# DD2090_4CAM_FFC_USB.net
KiCad netlist of a schematic drawn in Altium Designer
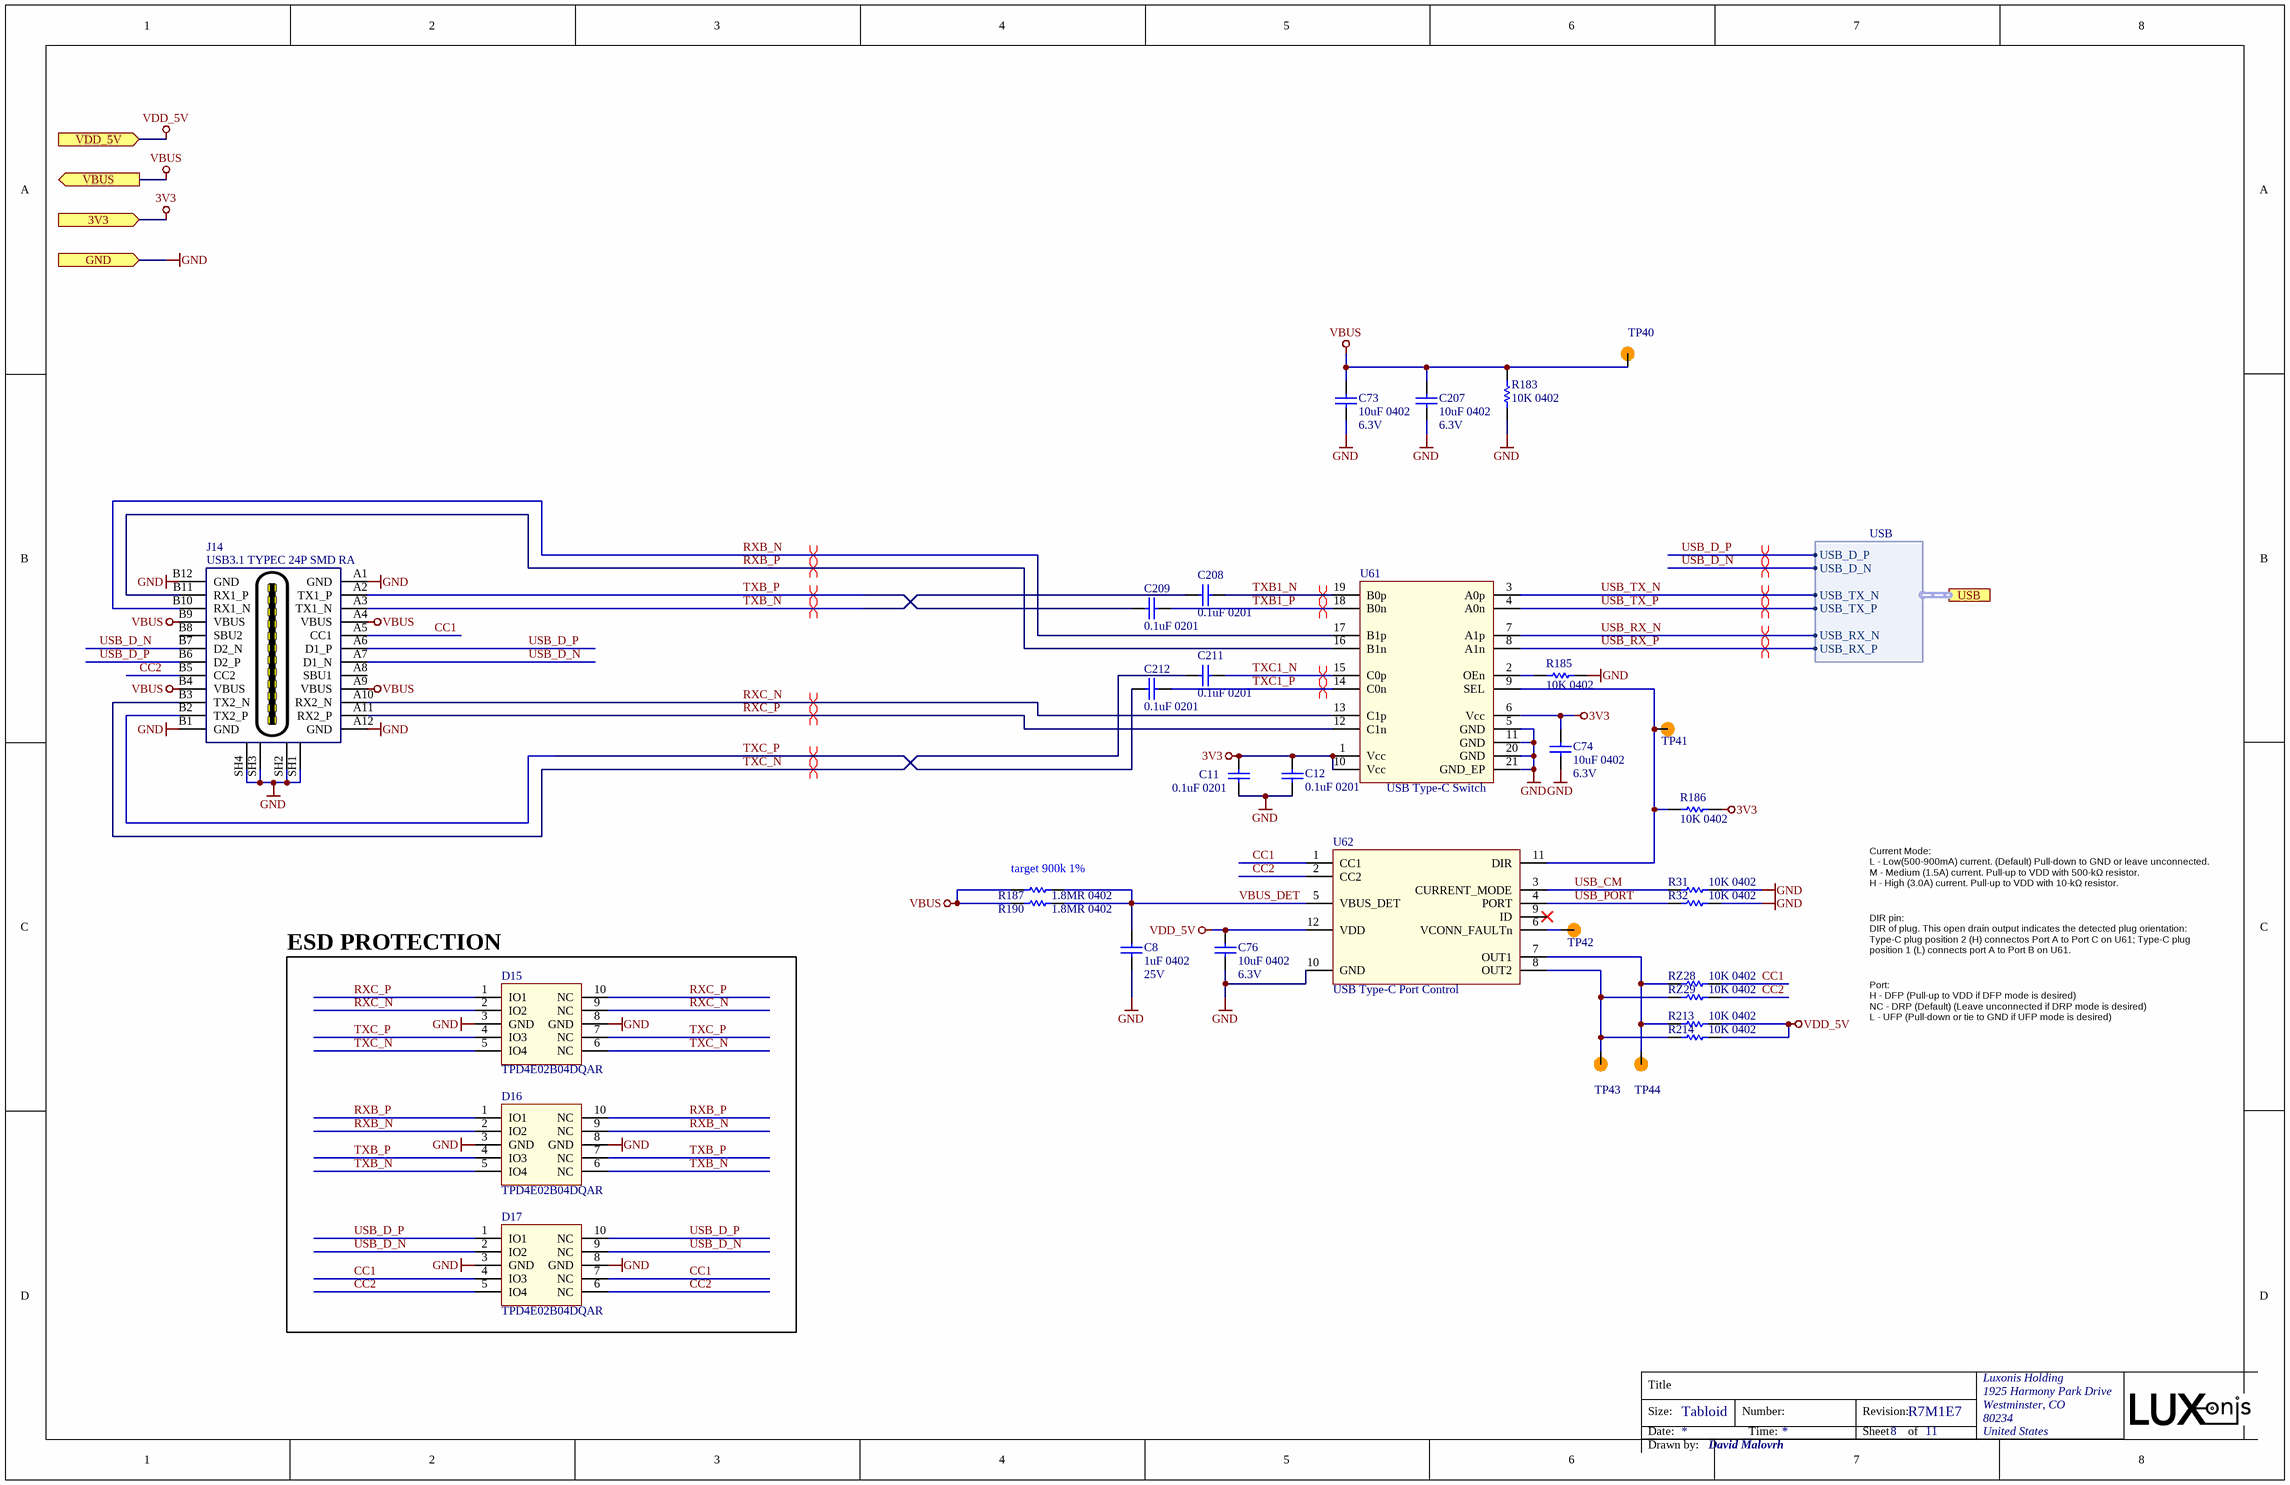
[diagram p0: DD2090_4CAM_FFC_USB.SchDoc]

(export (version "E")
  (design (tool "Eeschema 10.0.6"))
  (components
    (comp (ref "C8")
      (value "1uF 0402")
      (footprint "CAP_Altium_Vault_Generic:CAPC0402(1005)70_N")
      (description "CAP CER 1UF 25V X5R 0402 10%")
      (fields
        (field (name "TOLERANCE") "10%")
        (field (name "VOLTAGE") "25V")
        (field (name "VOLTAGE RATING") "25V")
      )
      (libsource (lib "LuxonisMaster") (part "GRM155R61E105KA12D"))
    )
    (comp (ref "C11")
      (value "0.1uF 0201")
      (footprint "CAP_Altium_Vault_Generic:CAPC0201(0603)33_L")
      (description "CAP CER 0.1UF 10V X5R 0201")
      (fields (field (name "TOLERANCE") "10%") (field (name "VOLTAGE") "10V"))
      (libsource (lib "LuxonisMaster") (part "GRM033R61A104KE15D"))
    )
    (comp (ref "C12")
      (value "0.1uF 0201")
      (footprint "CAP_Altium_Vault_Generic:CAPC0201(0603)33_L")
      (description "CAP CER 0.1UF 10V X5R 0201")
      (fields (field (name "TOLERANCE") "10%") (field (name "VOLTAGE") "10V"))
      (libsource (lib "LuxonisMaster") (part "GRM033R61A104KE15D"))
    )
    (comp (ref "C73")
      (value "10uF 0402")
      (footprint "CAP_Altium_Vault_Generic:CAPC0402(1005)70_N")
      (description "CAP CER 10UF 6.3V X5R 0402 20%")
      (fields (field (name "TOLERANCE") "20%") (field (name "VOLTAGE RATING") "6.3V"))
      (libsource (lib "LuxonisMaster") (part "GRM155R60J106ME15D"))
    )
    (comp (ref "C74")
      (value "10uF 0402")
      (footprint "CAP_Altium_Vault_Generic:CAPC0402(1005)70_N")
      (description "CAP CER 10UF 6.3V X5R 0402 20%")
      (fields (field (name "TOLERANCE") "20%") (field (name "VOLTAGE RATING") "6.3V"))
      (libsource (lib "LuxonisMaster") (part "GRM155R60J106ME15D"))
    )
    (comp (ref "C76")
      (value "10uF 0402")
      (footprint "CAP_Altium_Vault_Generic:CAPC0402(1005)70_N")
      (description "CAP CER 10UF 6.3V X5R 0402 20%")
      (fields (field (name "TOLERANCE") "20%") (field (name "VOLTAGE RATING") "6.3V"))
      (libsource (lib "LuxonisMaster") (part "GRM155R60J106ME15D"))
    )
    (comp (ref "C207")
      (value "10uF 0402")
      (footprint "CAP_Altium_Vault_Generic:CAPC0402(1005)70_N")
      (description "CAP CER 10UF 6.3V X5R 0402 20%")
      (fields (field (name "TOLERANCE") "20%") (field (name "VOLTAGE RATING") "6.3V"))
      (libsource (lib "LuxonisMaster") (part "GRM155R60J106ME15D"))
    )
    (comp (ref "C208")
      (value "0.1uF 0201")
      (footprint "CAP_Altium_Vault_Generic:CAPC0201(0603)33_L")
      (description "CAP CER 0.1UF 10V X5R 0201")
      (fields (field (name "TOLERANCE") "10%") (field (name "VOLTAGE") "10V"))
      (libsource (lib "LuxonisMaster") (part "GRM033R61A104KE15D"))
    )
    (comp (ref "C209")
      (value "0.1uF 0201")
      (footprint "CAP_Altium_Vault_Generic:CAPC0201(0603)33_L")
      (description "CAP CER 0.1UF 10V X5R 0201")
      (fields (field (name "TOLERANCE") "10%") (field (name "VOLTAGE") "10V"))
      (libsource (lib "LuxonisMaster") (part "GRM033R61A104KE15D"))
    )
    (comp (ref "C211")
      (value "0.1uF 0201")
      (footprint "CAP_Altium_Vault_Generic:CAPC0201(0603)33_L")
      (description "CAP CER 0.1UF 10V X5R 0201")
      (fields (field (name "TOLERANCE") "10%") (field (name "VOLTAGE") "10V"))
      (libsource (lib "LuxonisMaster") (part "GRM033R61A104KE15D"))
    )
    (comp (ref "C212")
      (value "0.1uF 0201")
      (footprint "CAP_Altium_Vault_Generic:CAPC0201(0603)33_L")
      (description "CAP CER 0.1UF 10V X5R 0201")
      (fields (field (name "TOLERANCE") "10%") (field (name "VOLTAGE") "10V"))
      (libsource (lib "LuxonisMaster") (part "GRM033R61A104KE15D"))
    )
    (comp (ref "D15")
      (value "TPD4E02B04DQAR")
      (footprint "TPD4E02B04DQAR")
      (libsource (lib "LuxonisMaster") (part "TPD4E02B04DQAR"))
    )
    (comp (ref "D16")
      (value "TPD4E02B04DQAR")
      (footprint "TPD4E02B04DQAR")
      (libsource (lib "LuxonisMaster") (part "TPD4E02B04DQAR"))
    )
    (comp (ref "D17")
      (value "TPD4E02B04DQAR")
      (footprint "TPD4E02B04DQAR")
      (libsource (lib "LuxonisMaster") (part "TPD4E02B04DQAR"))
    )
    (comp (ref "J14")
      (value "USB3.1 TYPEC 24P SMD RA")
      (footprint "LuxonisMaster:105450-0101")
      (description "CONN RCP USB3.1 TYPEC 24P SMD RA")
      (libsource (lib "LuxonisMaster") (part "105450-0101"))
    )
    (comp (ref "R31")
      (value "10K 0402")
      (footprint "RES_Altium_Vault_Generic:RESC0402(1005)_N")
      (fields (field (name "TOLERANCE") "1%"))
      (libsource (lib "LuxonisMaster") (part "RC0402FR-1310KL"))
    )
    (comp (ref "R32")
      (value "10K 0402")
      (footprint "RES_Altium_Vault_Generic:RESC0402(1005)_N")
      (fields (field (name "TOLERANCE") "1%"))
      (libsource (lib "LuxonisMaster") (part "RC0402FR-1310KL"))
    )
    (comp (ref "R183")
      (value "10K 0402")
      (footprint "RES_Altium_Vault_Generic:RESC0402(1005)_N")
      (fields (field (name "TOLERANCE") "1%"))
      (libsource (lib "LuxonisMaster") (part "RC0402FR-1310KL"))
    )
    (comp (ref "R185")
      (value "10K 0402")
      (footprint "RES_Altium_Vault_Generic:RESC0402(1005)_N")
      (fields (field (name "TOLERANCE") "1%"))
      (libsource (lib "LuxonisMaster") (part "RC0402FR-1310KL"))
    )
    (comp (ref "R186")
      (value "10K 0402")
      (footprint "RES_Altium_Vault_Generic:RESC0402(1005)_N")
      (fields (field (name "TOLERANCE") "1%"))
      (libsource (lib "LuxonisMaster") (part "RC0402FR-1310KL"))
    )
    (comp (ref "R187")
      (value "1.8MR 0402")
      (footprint "RES_Altium_Vault_Generic:RESC0402(1005)_N")
      (description "RES SMD 1.8M OHM 1% 1/16W 0402")
      (fields (field (name "TOLERANCE") "1%"))
      (libsource (lib "LuxonisMaster") (part "CRCW04021M80FKED"))
    )
    (comp (ref "R190")
      (value "1.8MR 0402")
      (footprint "RES_Altium_Vault_Generic:RESC0402(1005)_N")
      (description "RES SMD 1.8M OHM 1% 1/16W 0402")
      (fields (field (name "TOLERANCE") "1%"))
      (libsource (lib "LuxonisMaster") (part "CRCW04021M80FKED"))
    )
    (comp (ref "R213")
      (value "10K 0402")
      (footprint "RES_Altium_Vault_Generic:RESC0402(1005)_N")
      (fields (field (name "TOLERANCE") "1%"))
      (libsource (lib "LuxonisMaster") (part "RC0402FR-1310KL"))
    )
    (comp (ref "R214")
      (value "10K 0402")
      (footprint "RES_Altium_Vault_Generic:RESC0402(1005)_N")
      (fields (field (name "TOLERANCE") "1%"))
      (libsource (lib "LuxonisMaster") (part "RC0402FR-1310KL"))
    )
    (comp (ref "RZ28")
      (value "10K 0402")
      (footprint "RES_Altium_Vault_Generic:RESC0402(1005)_N")
      (fields (field (name "TOLERANCE") "1%"))
      (libsource (lib "LuxonisMaster") (part "RC0402FR-1310KL"))
    )
    (comp (ref "RZ29")
      (value "10K 0402")
      (footprint "RES_Altium_Vault_Generic:RESC0402(1005)_N")
      (fields (field (name "TOLERANCE") "1%"))
      (libsource (lib "LuxonisMaster") (part "RC0402FR-1310KL"))
    )
    (comp (ref "TP40")
      (value "TP100_200_NS")
      (footprint "LuxonisMaster:TP100_200_NS")
      (libsource (lib "LuxonisMaster") (part "TEST_POINT"))
    )
    (comp (ref "TP41")
      (value "TP100_200_NS")
      (footprint "LuxonisMaster:TP100_200_NS")
      (libsource (lib "LuxonisMaster") (part "TEST_POINT"))
    )
    (comp (ref "TP42")
      (value "TP100_200_NS")
      (footprint "LuxonisMaster:TP100_200_NS")
      (libsource (lib "LuxonisMaster") (part "TEST_POINT"))
    )
    (comp (ref "TP43")
      (value "TP100_200_NS")
      (footprint "LuxonisMaster:TP100_200_NS")
      (libsource (lib "LuxonisMaster") (part "TEST_POINT"))
    )
    (comp (ref "TP44")
      (value "TP100_200_NS")
      (footprint "LuxonisMaster:TP100_200_NS")
      (libsource (lib "LuxonisMaster") (part "TEST_POINT"))
    )
    (comp (ref "U61")
      (value "USB Type-C Switch")
      (footprint "CBTL02043A")
      (libsource (lib "LuxonisMaster") (part "CBTL02043A"))
    )
    (comp (ref "U62")
      (value "USB Type-C Port Control")
      (footprint "LuxonisMaster:TUSB321RWBR")
      (description "IC USB PORT CONTROL TYPE-C 12X2Q")
      (libsource (lib "LuxonisMaster") (part "TUSB321RWBR"))
    )
  )
  (nets
    (net (code "2") (name "/CC1") (class "Default")
      (node (ref "D17") (pin "4") (pinfunction "IO3_4") (pintype "passive"))
      (node (ref "D17") (pin "7") (pinfunction "NC_7") (pintype "passive"))
      (node (ref "J14") (pin "A5") (pinfunction "CC1_A5") (pintype "passive"))
      (node (ref "RZ28") (pin "2") (pinfunction "2_2") (pintype "passive"))
      (node (ref "U62") (pin "1") (pinfunction "CC1_1") (pintype "passive"))
    )
    (net (code "3") (name "/CC2") (class "Default")
      (node (ref "D17") (pin "5") (pinfunction "IO4_5") (pintype "passive"))
      (node (ref "D17") (pin "6") (pinfunction "NC_6") (pintype "passive"))
      (node (ref "J14") (pin "B5") (pinfunction "CC2_B5") (pintype "passive"))
      (node (ref "RZ29") (pin "2") (pinfunction "2_2") (pintype "passive"))
      (node (ref "U62") (pin "2") (pinfunction "CC2_2") (pintype "passive"))
    )
    (net (code "4") (name "/RXB_N") (class "Default")
      (node (ref "D16") (pin "2") (pinfunction "IO2_2") (pintype "passive"))
      (node (ref "D16") (pin "9") (pinfunction "NC_9") (pintype "passive"))
      (node (ref "J14") (pin "B10") (pinfunction "RX1_N_B10") (pintype "passive"))
      (node (ref "U61") (pin "17") (pinfunction "B1p_17") (pintype "passive"))
    )
    (net (code "5") (name "/RXB_P") (class "Default")
      (node (ref "D16") (pin "1") (pinfunction "IO1_1") (pintype "passive"))
      (node (ref "D16") (pin "10") (pinfunction "NC_10") (pintype "passive"))
      (node (ref "J14") (pin "B11") (pinfunction "RX1_P_B11") (pintype "passive"))
      (node (ref "U61") (pin "16") (pinfunction "B1n_16") (pintype "passive"))
    )
    (net (code "6") (name "/RXC_N") (class "Default")
      (node (ref "D15") (pin "2") (pinfunction "IO2_2") (pintype "passive"))
      (node (ref "D15") (pin "9") (pinfunction "NC_9") (pintype "passive"))
      (node (ref "J14") (pin "A10") (pinfunction "RX2_N_A10") (pintype "passive"))
      (node (ref "U61") (pin "13") (pinfunction "C1p_13") (pintype "passive"))
    )
    (net (code "7") (name "/RXC_P") (class "Default")
      (node (ref "D15") (pin "1") (pinfunction "IO1_1") (pintype "passive"))
      (node (ref "D15") (pin "10") (pinfunction "NC_10") (pintype "passive"))
      (node (ref "J14") (pin "A11") (pinfunction "RX2_P_A11") (pintype "passive"))
      (node (ref "U61") (pin "12") (pinfunction "C1n_12") (pintype "passive"))
    )
    (net (code "8") (name "/TXB1_N") (class "Default")
      (node (ref "C208") (pin "2") (pinfunction "2_2") (pintype "passive"))
      (node (ref "U61") (pin "19") (pinfunction "B0p_19") (pintype "passive"))
    )
    (net (code "9") (name "/TXB1_P") (class "Default")
      (node (ref "C209") (pin "2") (pinfunction "2_2") (pintype "passive"))
      (node (ref "U61") (pin "18") (pinfunction "B0n_18") (pintype "passive"))
    )
    (net (code "10") (name "/TXB_N") (class "Default")
      (node (ref "C208") (pin "1") (pinfunction "1_1") (pintype "passive"))
      (node (ref "D16") (pin "5") (pinfunction "IO4_5") (pintype "passive"))
      (node (ref "D16") (pin "6") (pinfunction "NC_6") (pintype "passive"))
      (node (ref "J14") (pin "A3") (pinfunction "TX1_N_A3") (pintype "passive"))
    )
    (net (code "11") (name "/TXB_P") (class "Default")
      (node (ref "C209") (pin "1") (pinfunction "1_1") (pintype "passive"))
      (node (ref "D16") (pin "4") (pinfunction "IO3_4") (pintype "passive"))
      (node (ref "D16") (pin "7") (pinfunction "NC_7") (pintype "passive"))
      (node (ref "J14") (pin "A2") (pinfunction "TX1_P_A2") (pintype "passive"))
    )
    (net (code "12") (name "/TXC1_N") (class "Default")
      (node (ref "C211") (pin "2") (pinfunction "2_2") (pintype "passive"))
      (node (ref "U61") (pin "15") (pinfunction "C0p_15") (pintype "passive"))
    )
    (net (code "13") (name "/TXC1_P") (class "Default")
      (node (ref "C212") (pin "2") (pinfunction "2_2") (pintype "passive"))
      (node (ref "U61") (pin "14") (pinfunction "C0n_14") (pintype "passive"))
    )
    (net (code "14") (name "/TXC_N") (class "Default")
      (node (ref "C211") (pin "1") (pinfunction "1_1") (pintype "passive"))
      (node (ref "D15") (pin "5") (pinfunction "IO4_5") (pintype "passive"))
      (node (ref "D15") (pin "6") (pinfunction "NC_6") (pintype "passive"))
      (node (ref "J14") (pin "B3") (pinfunction "TX2_N_B3") (pintype "passive"))
    )
    (net (code "15") (name "/TXC_P") (class "Default")
      (node (ref "C212") (pin "1") (pinfunction "1_1") (pintype "passive"))
      (node (ref "D15") (pin "4") (pinfunction "IO3_4") (pintype "passive"))
      (node (ref "D15") (pin "7") (pinfunction "NC_7") (pintype "passive"))
      (node (ref "J14") (pin "B2") (pinfunction "TX2_P_B2") (pintype "passive"))
    )
    (net (code "16") (name "/USB_CM") (class "Default")
      (node (ref "R31") (pin "1") (pinfunction "1_1") (pintype "passive"))
      (node (ref "U62") (pin "3") (pinfunction "CURRENT_MODE_3") (pintype "passive"))
    )
    (net (code "17") (name "/USB_D_N") (class "Default")
      (node (ref "D17") (pin "2") (pinfunction "IO2_2") (pintype "passive"))
      (node (ref "D17") (pin "9") (pinfunction "NC_9") (pintype "passive"))
      (node (ref "J14") (pin "A7") (pinfunction "D1_N_A7") (pintype "passive"))
      (node (ref "J14") (pin "B7") (pinfunction "D2_N_B7") (pintype "passive"))
    )
    (net (code "18") (name "/USB_D_P") (class "Default")
      (node (ref "D17") (pin "1") (pinfunction "IO1_1") (pintype "passive"))
      (node (ref "D17") (pin "10") (pinfunction "NC_10") (pintype "passive"))
      (node (ref "J14") (pin "A6") (pinfunction "D1_P_A6") (pintype "passive"))
      (node (ref "J14") (pin "B6") (pinfunction "D2_P_B6") (pintype "passive"))
    )
    (net (code "19") (name "/USB_PORT") (class "Default")
      (node (ref "R32") (pin "1") (pinfunction "1_1") (pintype "passive"))
      (node (ref "U62") (pin "4") (pinfunction "PORT_4") (pintype "passive"))
    )
    (net (code "20") (name "/USB_RX_N") (class "Default")
      (node (ref "U61") (pin "7") (pinfunction "A1p_7") (pintype "passive"))
    )
    (net (code "21") (name "/USB_RX_P") (class "Default")
      (node (ref "U61") (pin "8") (pinfunction "A1n_8") (pintype "passive"))
    )
    (net (code "22") (name "/USB_TX_N") (class "Default")
      (node (ref "U61") (pin "3") (pinfunction "A0p_3") (pintype "passive"))
    )
    (net (code "23") (name "/USB_TX_P") (class "Default")
      (node (ref "U61") (pin "4") (pinfunction "A0n_4") (pintype "passive"))
    )
    (net (code "24") (name "/VBUS_DET") (class "Default")
      (node (ref "C8") (pin "2") (pinfunction "2_2") (pintype "passive"))
      (node (ref "R187") (pin "2") (pinfunction "2_2") (pintype "passive"))
      (node (ref "R190") (pin "2") (pinfunction "2_2") (pintype "passive"))
      (node (ref "U62") (pin "5") (pinfunction "VBUS_DET_5") (pintype "passive"))
    )
    (net (code "26") (name "3V3") (class "Default")
      (node (ref "C11") (pin "2") (pinfunction "2_2") (pintype "passive"))
      (node (ref "C12") (pin "2") (pinfunction "2_2") (pintype "passive"))
      (node (ref "C74") (pin "2") (pinfunction "2_2") (pintype "passive"))
      (node (ref "R186") (pin "2") (pinfunction "2_2") (pintype "passive"))
      (node (ref "U61") (pin "1") (pinfunction "Vcc_1") (pintype "passive"))
      (node (ref "U61") (pin "10") (pinfunction "Vcc_10") (pintype "passive"))
      (node (ref "U61") (pin "6") (pinfunction "Vcc_6") (pintype "passive"))
    )
    (net (code "27") (name "GND") (class "Default")
      (node (ref "C11") (pin "1") (pinfunction "1_1") (pintype "passive"))
      (node (ref "C12") (pin "1") (pinfunction "1_1") (pintype "passive"))
      (node (ref "C207") (pin "1") (pinfunction "1_1") (pintype "passive"))
      (node (ref "C73") (pin "1") (pinfunction "1_1") (pintype "passive"))
      (node (ref "C74") (pin "1") (pinfunction "1_1") (pintype "passive"))
      (node (ref "C76") (pin "1") (pinfunction "1_1") (pintype "passive"))
      (node (ref "C8") (pin "1") (pinfunction "1_1") (pintype "passive"))
      (node (ref "D15") (pin "3") (pinfunction "GND_3") (pintype "passive"))
      (node (ref "D15") (pin "8") (pinfunction "GND_8") (pintype "passive"))
      (node (ref "D16") (pin "3") (pinfunction "GND_3") (pintype "passive"))
      (node (ref "D16") (pin "8") (pinfunction "GND_8") (pintype "passive"))
      (node (ref "D17") (pin "3") (pinfunction "GND_3") (pintype "passive"))
      (node (ref "D17") (pin "8") (pinfunction "GND_8") (pintype "passive"))
      (node (ref "J14") (pin "A1") (pinfunction "GND_A1") (pintype "passive"))
      (node (ref "J14") (pin "A12") (pinfunction "GND_A12") (pintype "passive"))
      (node (ref "J14") (pin "B1") (pinfunction "GND_B1") (pintype "passive"))
      (node (ref "J14") (pin "B12") (pinfunction "GND_B12") (pintype "passive"))
      (node (ref "J14") (pin "SH1") (pinfunction "SH_SH1") (pintype "passive"))
      (node (ref "J14") (pin "SH2") (pinfunction "SH_SH2") (pintype "passive"))
      (node (ref "J14") (pin "SH3") (pinfunction "SH_SH3") (pintype "passive"))
      (node (ref "J14") (pin "SH4") (pinfunction "SH_SH4") (pintype "passive"))
      (node (ref "R183") (pin "1") (pinfunction "1_1") (pintype "passive"))
      (node (ref "R185") (pin "2") (pinfunction "2_2") (pintype "passive"))
      (node (ref "R31") (pin "2") (pinfunction "2_2") (pintype "passive"))
      (node (ref "R32") (pin "2") (pinfunction "2_2") (pintype "passive"))
      (node (ref "U61") (pin "11") (pinfunction "GND_11") (pintype "passive"))
      (node (ref "U61") (pin "20") (pinfunction "GND_20") (pintype "passive"))
      (node (ref "U61") (pin "21") (pinfunction "GND_EP_21") (pintype "passive"))
      (node (ref "U61") (pin "5") (pinfunction "GND_5") (pintype "passive"))
      (node (ref "U62") (pin "10") (pinfunction "GND_10") (pintype "passive"))
    )
    (net (code "28") (name "Net-(U61-OEn)") (class "Default")
      (node (ref "R185") (pin "1") (pinfunction "1_1") (pintype "passive"))
      (node (ref "U61") (pin "2") (pinfunction "OEn_2") (pintype "passive"))
    )
    (net (code "29") (name "Net-(U61-SEL)") (class "Default")
      (node (ref "R186") (pin "1") (pinfunction "1_1") (pintype "passive"))
      (node (ref "TP41") (pin "1") (pintype "passive"))
      (node (ref "U61") (pin "9") (pinfunction "SEL_9") (pintype "passive"))
      (node (ref "U62") (pin "11") (pinfunction "DIR_11") (pintype "passive"))
    )
    (net (code "30") (name "Net-(U62-OUT1)") (class "Default")
      (node (ref "R213") (pin "1") (pinfunction "1_1") (pintype "passive"))
      (node (ref "RZ28") (pin "1") (pinfunction "1_1") (pintype "passive"))
      (node (ref "TP44") (pin "1") (pintype "passive"))
      (node (ref "U62") (pin "7") (pinfunction "OUT1_7") (pintype "passive"))
    )
    (net (code "31") (name "Net-(U62-OUT2)") (class "Default")
      (node (ref "R214") (pin "1") (pinfunction "1_1") (pintype "passive"))
      (node (ref "RZ29") (pin "1") (pinfunction "1_1") (pintype "passive"))
      (node (ref "TP43") (pin "1") (pintype "passive"))
      (node (ref "U62") (pin "8") (pinfunction "OUT2_8") (pintype "passive"))
    )
    (net (code "32") (name "Net-(U62-VCONN_FAULTn)") (class "Default")
      (node (ref "TP42") (pin "1") (pintype "passive"))
      (node (ref "U62") (pin "6") (pinfunction "VCONN_FAULTn_6") (pintype "passive"))
    )
    (net (code "33") (name "VBUS") (class "Default")
      (node (ref "C207") (pin "2") (pinfunction "2_2") (pintype "passive"))
      (node (ref "C73") (pin "2") (pinfunction "2_2") (pintype "passive"))
      (node (ref "J14") (pin "A4") (pinfunction "VBUS_A4") (pintype "passive"))
      (node (ref "J14") (pin "A9") (pinfunction "VBUS_A9") (pintype "passive"))
      (node (ref "J14") (pin "B4") (pinfunction "VBUS_B4") (pintype "passive"))
      (node (ref "J14") (pin "B9") (pinfunction "VBUS_B9") (pintype "passive"))
      (node (ref "R183") (pin "2") (pinfunction "2_2") (pintype "passive"))
      (node (ref "R187") (pin "1") (pinfunction "1_1") (pintype "passive"))
      (node (ref "R190") (pin "1") (pinfunction "1_1") (pintype "passive"))
      (node (ref "TP40") (pin "1") (pintype "passive"))
    )
    (net (code "34") (name "VDD_5V") (class "Default")
      (node (ref "C76") (pin "2") (pinfunction "2_2") (pintype "passive"))
      (node (ref "R213") (pin "2") (pinfunction "2_2") (pintype "passive"))
      (node (ref "R214") (pin "2") (pinfunction "2_2") (pintype "passive"))
      (node (ref "U62") (pin "12") (pinfunction "VDD_12") (pintype "passive"))
    )
    (net (code "35") (name "unconnected-(J14-SBU1-PadA8)") (class "Default")
      (node (ref "J14") (pin "A8") (pinfunction "SBU1_A8") (pintype "passive"))
    )
    (net (code "36") (name "unconnected-(J14-SBU2-PadB8)") (class "Default")
      (node (ref "J14") (pin "B8") (pinfunction "SBU2_B8") (pintype "passive"))
    )
    (net (code "37") (name "unconnected-(U62-ID-Pad9)") (class "Default")
      (node (ref "U62") (pin "9") (pinfunction "ID_9") (pintype "passive+no_connect"))
    )
  )
)
